# Peripherals.net
KiCad netlist of a schematic drawn in Altium Designer
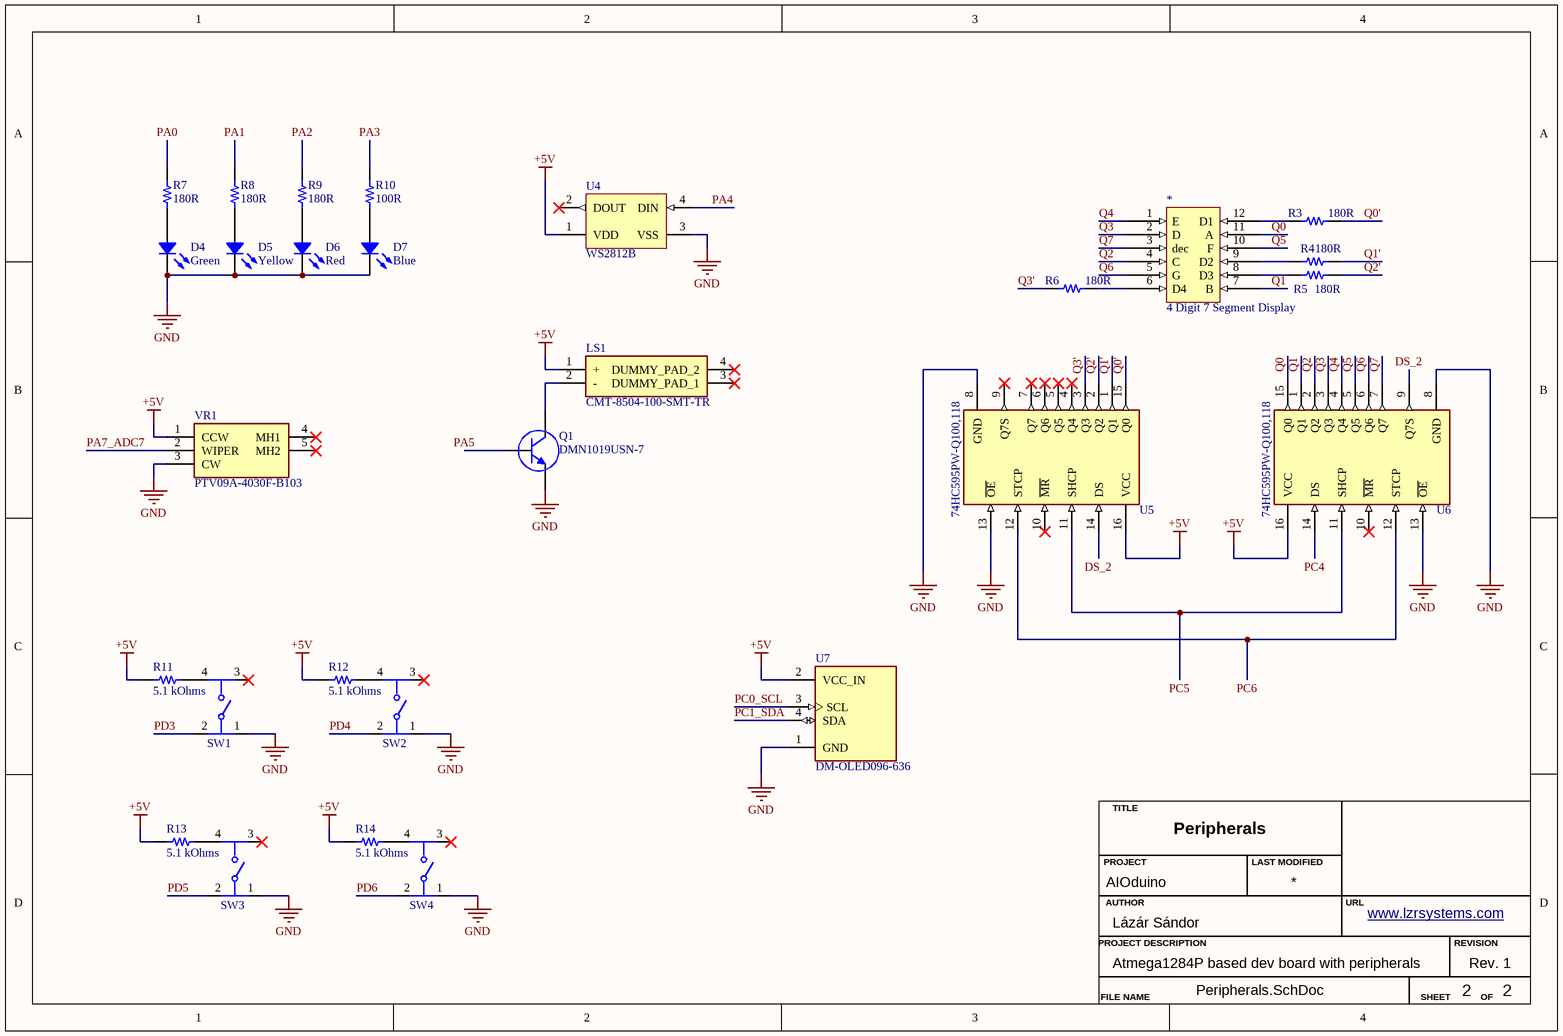
[diagram p0: Peripherals.SchDoc]

(export (version "E")
  (design (tool "Eeschema 10.0.6"))
  (components
    (comp (ref "*")
      (value "4 Digit 7 Segment Display")
      (footprint "4 Digit 7 Segment Display -Footprint-1")
      (description "3461AS 4 digit 7 segment display")
      (libsource (lib "Sandor Lazar") (part "4 Digit 7 Segment Display -Symbol-1"))
    )
    (comp (ref "D4")
      (value "Green")
      (footprint "LED 1206_3216 GREEN")
      (description "LED GREEN CLEAR 1206 SMD")
      (fields
        (field (name "PART NUMBER") "SML-LX1206SUGC-TR")
        (field (name "MANUFACTURER") "Lumex Opto/Components Inc.")
      )
      (libsource (lib "Celestial Altium Library - altium_library") (part "LED"))
    )
    (comp (ref "D5")
      (value "Yellow")
      (footprint "LED 1206_3216 YELLOW")
      (description "LED YELLOW CLEAR 1206 SMD")
      (fields (field (name "PART NUMBER") "SM1206NYC-IL") (field (name "MANUFACTURER") "Bivar Inc."))
      (libsource (lib "Celestial Altium Library - altium_library") (part "LED"))
    )
    (comp (ref "D6")
      (value "Red")
      (footprint "LED 1206_3216 RED")
      (description "LED RED CLEAR 1206 SMD")
      (fields
        (field (name "PART NUMBER") "BL-HUF33J-AV-TRB")
        (field (name "MANUFACTURER") "American Bright Optoelectronics Corporation")
      )
      (libsource (lib "Celestial Altium Library - altium_library") (part "LED"))
    )
    (comp (ref "D7")
      (value "Blue")
      (footprint "LED 1206_3216 BLUE")
      (description "LED BLUE CLEAR 1206 SMD")
      (fields
        (field (name "PART NUMBER") "SML-LX1206USBC-TR")
        (field (name "MANUFACTURER") "Lumex Opto/Components Inc.")
      )
      (libsource (lib "Celestial Altium Library - altium_library") (part "LED"))
    )
    (comp (ref "LS1")
      (value "CMT-8504-100-SMT-TR")
      (footprint "SamacSys:CMT8504100SMTTR")
      (description "Loudspeaker or Buzzer")
      (fields (field (name "MOUSER PART NUMBER") "490-CMT-8504100SMTTR"))
      (libsource (lib "*") (part "CMT-8504-100-SMT-TR"))
    )
    (comp (ref "Q1")
      (value "DMN1019USN-7")
      (footprint "FP-SC59-MFG")
      (libsource (lib "Sandor Lazar") (part "TRANS-NPN-3"))
    )
    (comp (ref "R3")
      (value "180R")
      (footprint "RES 0805_2012")
      (description "RES SMD 180 OHM 1% 1/2W 0805")
      (fields (field (name "PART NUMBER") "CRCW0805180RFKEAHP") (field (name "MANUFACTURER") "Vishay Dale"))
      (libsource (lib "Celestial Altium Library - altium_library") (part "Resistor"))
    )
    (comp (ref "R4")
      (value "180R")
      (footprint "RES 0805_2012")
      (description "RES SMD 180 OHM 1% 1/2W 0805")
      (fields (field (name "PART NUMBER") "CRCW0805180RFKEAHP") (field (name "MANUFACTURER") "Vishay Dale"))
      (libsource (lib "Celestial Altium Library - altium_library") (part "Resistor"))
    )
    (comp (ref "R5")
      (value "180R")
      (footprint "RES 0805_2012")
      (description "RES SMD 180 OHM 1% 1/2W 0805")
      (fields (field (name "PART NUMBER") "CRCW0805180RFKEAHP") (field (name "MANUFACTURER") "Vishay Dale"))
      (libsource (lib "Celestial Altium Library - altium_library") (part "Resistor"))
    )
    (comp (ref "R6")
      (value "180R")
      (footprint "RES 0805_2012")
      (description "RES SMD 180 OHM 1% 1/2W 0805")
      (fields (field (name "PART NUMBER") "CRCW0805180RFKEAHP") (field (name "MANUFACTURER") "Vishay Dale"))
      (libsource (lib "Celestial Altium Library - altium_library") (part "Resistor"))
    )
    (comp (ref "R7")
      (value "180R")
      (footprint "RES 0805_2012")
      (description "RES SMD 180 OHM 1% 1/2W 0805")
      (fields (field (name "PART NUMBER") "CRCW0805180RFKEAHP") (field (name "MANUFACTURER") "Vishay Dale"))
      (libsource (lib "Celestial Altium Library - altium_library") (part "Resistor"))
    )
    (comp (ref "R8")
      (value "180R")
      (footprint "RES 0805_2012")
      (description "RES SMD 180 OHM 1% 1/2W 0805")
      (fields (field (name "PART NUMBER") "CRCW0805180RFKEAHP") (field (name "MANUFACTURER") "Vishay Dale"))
      (libsource (lib "Celestial Altium Library - altium_library") (part "Resistor"))
    )
    (comp (ref "R9")
      (value "180R")
      (footprint "RES 0805_2012")
      (description "RES SMD 180 OHM 1% 1/2W 0805")
      (fields (field (name "PART NUMBER") "CRCW0805180RFKEAHP") (field (name "MANUFACTURER") "Vishay Dale"))
      (libsource (lib "Celestial Altium Library - altium_library") (part "Resistor"))
    )
    (comp (ref "R10")
      (value "100R")
      (footprint "RES 0805_2012")
      (description "RES SMD 100 OHM 1% 1/2W 0805")
      (fields (field (name "PART NUMBER") "RCS0805100RFKEA") (field (name "MANUFACTURER") "Vishay Dale"))
      (libsource (lib "Celestial Altium Library - altium_library") (part "Resistor"))
    )
    (comp (ref "R11")
      (value "5.1 kOhms")
      (footprint "RES 0805_2012")
      (description "RES 5.1K OHM 1% 1/8W 0805")
      (fields
        (field (name "PART NUMBER") "RMCF0805FT5K10")
        (field (name "MANUFACTURER") "Stackpole Electronics Inc")
      )
      (libsource (lib "Celestial Altium Library - altium_library") (part "Resistor"))
    )
    (comp (ref "R12")
      (value "5.1 kOhms")
      (footprint "RES 0805_2012")
      (description "RES 5.1K OHM 1% 1/8W 0805")
      (fields
        (field (name "PART NUMBER") "RMCF0805FT5K10")
        (field (name "MANUFACTURER") "Stackpole Electronics Inc")
      )
      (libsource (lib "Celestial Altium Library - altium_library") (part "Resistor"))
    )
    (comp (ref "R13")
      (value "5.1 kOhms")
      (footprint "RES 0805_2012")
      (description "RES 5.1K OHM 1% 1/8W 0805")
      (fields
        (field (name "PART NUMBER") "RMCF0805FT5K10")
        (field (name "MANUFACTURER") "Stackpole Electronics Inc")
      )
      (libsource (lib "Celestial Altium Library - altium_library") (part "Resistor"))
    )
    (comp (ref "R14")
      (value "5.1 kOhms")
      (footprint "RES 0805_2012")
      (description "RES 5.1K OHM 1% 1/8W 0805")
      (fields
        (field (name "PART NUMBER") "RMCF0805FT5K10")
        (field (name "MANUFACTURER") "Stackpole Electronics Inc")
      )
      (libsource (lib "Celestial Altium Library - altium_library") (part "Resistor"))
    )
    (comp (ref "SW1")
      (value "PTS526SK15SMTR2LFS")
      (footprint "FP-PTS526SK15SMTR2LFS-MFG")
      (description "Switch Tactile N.O. SPST Round Button Gull Wing 0.05A 12VDC 200000Cycles 2.45N SMD T/R")
      (libsource (lib "Sandor Lazar") (part "b8895f3f4cefb76e1819d2863dba89b"))
    )
    (comp (ref "SW2")
      (value "PTS526SK15SMTR2LFS")
      (footprint "FP-PTS526SK15SMTR2LFS-MFG")
      (description "Switch Tactile N.O. SPST Round Button Gull Wing 0.05A 12VDC 200000Cycles 2.45N SMD T/R")
      (libsource (lib "Sandor Lazar") (part "b8895f3f4cefb76e1819d2863dba89b"))
    )
    (comp (ref "SW3")
      (value "PTS526SK15SMTR2LFS")
      (footprint "FP-PTS526SK15SMTR2LFS-MFG")
      (description "Switch Tactile N.O. SPST Round Button Gull Wing 0.05A 12VDC 200000Cycles 2.45N SMD T/R")
      (libsource (lib "Sandor Lazar") (part "b8895f3f4cefb76e1819d2863dba89b"))
    )
    (comp (ref "SW4")
      (value "PTS526SK15SMTR2LFS")
      (footprint "FP-PTS526SK15SMTR2LFS-MFG")
      (description "Switch Tactile N.O. SPST Round Button Gull Wing 0.05A 12VDC 200000Cycles 2.45N SMD T/R")
      (libsource (lib "Sandor Lazar") (part "b8895f3f4cefb76e1819d2863dba89b"))
    )
    (comp (ref "U4")
      (value "WS2812B")
      (footprint "ADAI-WS2812B_V")
      (fields (field (name "MANUFACTURER") "Adafruit Industries"))
      (libsource (lib "Sandor Lazar") (part "ADAI-WS2812B-4"))
    )
    (comp (ref "U5")
      (value "74HC595PW-Q100,118")
      (footprint "FP-SOT403-1-IPC_A")
      (description "Serial In Parallel Out, HC/UH Series, 8-Bit, Right Direction, True Output, CMOS, PDSO16")
      (libsource (lib "") (part "35014dcb5ee7218ec7bb80311b7c79e_1"))
    )
    (comp (ref "U6")
      (value "74HC595PW-Q100,118")
      (footprint "FP-SOT403-1-IPC_A")
      (description "Serial In Parallel Out, HC/UH Series, 8-Bit, Right Direction, True Output, CMOS, PDSO16")
      (libsource (lib "Sandor Lazar") (part "35014dcb5ee7218ec7bb80311b7c79e"))
    )
    (comp (ref "U7")
      (value "DM-OLED096-636")
      (footprint "MODULE_DM-OLED096-636")
      (description "0.96â€ 128 X 64 MONOCHROME GRAPHIC OLED DISPLAY MODULE - I2C")
      (fields (field (name "MF") "Display Module"))
      (libsource (lib "Sandor Lazar") (part "DM-OLED096-636"))
    )
    (comp (ref "VR1")
      (value "PTV09A-4030F-B103")
      (footprint "SamacSys:PTV09A4030FB103")
      (description "Variable Resistor")
      (fields (field (name "MOUSER PART NUMBER") "652-PTV09A4030FB103"))
      (libsource (lib "*") (part "PTV09A-4030F-B103"))
    )
  )
  (nets
    (net (code "1") (name "+5V") (class "Default")
      (node (ref "LS1") (pin "1") (pinfunction "+_1") (pintype "passive"))
      (node (ref "R11") (pin "2") (pinfunction "2_2") (pintype "passive"))
      (node (ref "R12") (pin "2") (pinfunction "2_2") (pintype "passive"))
      (node (ref "R13") (pin "2") (pinfunction "2_2") (pintype "passive"))
      (node (ref "R14") (pin "2") (pinfunction "2_2") (pintype "passive"))
      (node (ref "U4") (pin "1") (pinfunction "VDD_1") (pintype "passive"))
      (node (ref "U5") (pin "16") (pinfunction "VCC_16") (pintype "passive"))
      (node (ref "U6") (pin "16") (pinfunction "VCC_16") (pintype "passive"))
      (node (ref "U7") (pin "2") (pinfunction "VCC_IN_2") (pintype "power_in"))
      (node (ref "VR1") (pin "1") (pinfunction "CCW_1") (pintype "passive"))
    )
    (net (code "2") (name "/DS_2") (class "Default")
      (node (ref "U5") (pin "14") (pinfunction "DS_14") (pintype "input"))
      (node (ref "U6") (pin "9") (pinfunction "Q7S_9") (pintype "output"))
    )
    (net (code "3") (name "/PA0") (class "Default")
      (node (ref "R7") (pin "2") (pinfunction "2_2") (pintype "passive"))
    )
    (net (code "4") (name "/PA1") (class "Default")
      (node (ref "R8") (pin "2") (pinfunction "2_2") (pintype "passive"))
    )
    (net (code "5") (name "/PA2") (class "Default")
      (node (ref "R9") (pin "2") (pinfunction "2_2") (pintype "passive"))
    )
    (net (code "6") (name "/PA3") (class "Default")
      (node (ref "R10") (pin "2") (pinfunction "2_2") (pintype "passive"))
    )
    (net (code "7") (name "/PA4") (class "Default")
      (node (ref "U4") (pin "4") (pinfunction "DIN_4") (pintype "input"))
    )
    (net (code "8") (name "/PA5") (class "Default")
      (node (ref "Q1") (pin "2") (pinfunction "B_2") (pintype "passive"))
    )
    (net (code "9") (name "/PA7_ADC7") (class "Default")
      (node (ref "VR1") (pin "2") (pinfunction "WIPER_2") (pintype "passive"))
    )
    (net (code "10") (name "/PC0_SCL") (class "Default")
      (node (ref "U7") (pin "3") (pinfunction "SCL_3") (pintype "input"))
    )
    (net (code "11") (name "/PC1_SDA") (class "Default")
      (node (ref "U7") (pin "4") (pinfunction "SDA_4") (pintype "bidirectional"))
    )
    (net (code "12") (name "/PC4") (class "Default")
      (node (ref "U6") (pin "14") (pinfunction "DS_14") (pintype "input"))
    )
    (net (code "13") (name "/PC5") (class "Default")
      (node (ref "U5") (pin "11") (pinfunction "SHCP_11") (pintype "input"))
      (node (ref "U6") (pin "11") (pinfunction "SHCP_11") (pintype "input"))
    )
    (net (code "14") (name "/PC6") (class "Default")
      (node (ref "U5") (pin "12") (pinfunction "STCP_12") (pintype "input"))
      (node (ref "U6") (pin "12") (pinfunction "STCP_12") (pintype "input"))
    )
    (net (code "15") (name "/PD3") (class "Default")
      (node (ref "SW1") (pin "2") (pinfunction "2_2") (pintype "passive"))
    )
    (net (code "16") (name "/PD4") (class "Default")
      (node (ref "SW2") (pin "2") (pinfunction "2_2") (pintype "passive"))
    )
    (net (code "17") (name "/PD5") (class "Default")
      (node (ref "SW3") (pin "2") (pinfunction "2_2") (pintype "passive"))
    )
    (net (code "18") (name "/PD6") (class "Default")
      (node (ref "SW4") (pin "2") (pinfunction "2_2") (pintype "passive"))
    )
    (net (code "19") (name "/Q0") (class "Default")
      (node (ref "*") (pin "11") (pinfunction "A_11") (pintype "input"))
      (node (ref "U6") (pin "15") (pinfunction "Q0_15") (pintype "output"))
    )
    (net (code "20") (name "/Q0'") (class "Default")
      (node (ref "R3") (pin "1") (pinfunction "1_1") (pintype "passive"))
      (node (ref "U5") (pin "15") (pinfunction "Q0_15") (pintype "output"))
    )
    (net (code "21") (name "/Q1") (class "Default")
      (node (ref "*") (pin "7") (pinfunction "B_7") (pintype "input"))
      (node (ref "U6") (pin "1") (pinfunction "Q1_1") (pintype "output"))
    )
    (net (code "22") (name "/Q1'") (class "Default")
      (node (ref "R4") (pin "2") (pinfunction "2_2") (pintype "passive"))
      (node (ref "U5") (pin "1") (pinfunction "Q1_1") (pintype "output"))
    )
    (net (code "23") (name "/Q2") (class "Default")
      (node (ref "*") (pin "4") (pinfunction "C_4") (pintype "input"))
      (node (ref "U6") (pin "2") (pinfunction "Q2_2") (pintype "output"))
    )
    (net (code "24") (name "/Q2'") (class "Default")
      (node (ref "R5") (pin "2") (pinfunction "2_2") (pintype "passive"))
      (node (ref "U5") (pin "2") (pinfunction "Q2_2") (pintype "output"))
    )
    (net (code "25") (name "/Q3") (class "Default")
      (node (ref "*") (pin "2") (pinfunction "D_2") (pintype "input"))
      (node (ref "U6") (pin "3") (pinfunction "Q3_3") (pintype "output"))
    )
    (net (code "26") (name "/Q3'") (class "Default")
      (node (ref "R6") (pin "2") (pinfunction "2_2") (pintype "passive"))
      (node (ref "U5") (pin "3") (pinfunction "Q3_3") (pintype "output"))
    )
    (net (code "27") (name "/Q4") (class "Default")
      (node (ref "*") (pin "1") (pinfunction "E_1") (pintype "input"))
      (node (ref "U6") (pin "4") (pinfunction "Q4_4") (pintype "output"))
    )
    (net (code "28") (name "/Q5") (class "Default")
      (node (ref "*") (pin "10") (pinfunction "F_10") (pintype "input"))
      (node (ref "U6") (pin "5") (pinfunction "Q5_5") (pintype "output"))
    )
    (net (code "29") (name "/Q6") (class "Default")
      (node (ref "*") (pin "5") (pinfunction "G_5") (pintype "input"))
      (node (ref "U6") (pin "6") (pinfunction "Q6_6") (pintype "output"))
    )
    (net (code "30") (name "/Q7") (class "Default")
      (node (ref "*") (pin "3") (pinfunction "dec_3") (pintype "input"))
      (node (ref "U6") (pin "7") (pinfunction "Q7_7") (pintype "output"))
    )
    (net (code "31") (name "GND") (class "Default")
      (node (ref "D4") (pin "2") (pinfunction "2_2") (pintype "passive"))
      (node (ref "D5") (pin "2") (pinfunction "2_2") (pintype "passive"))
      (node (ref "D6") (pin "2") (pinfunction "2_2") (pintype "passive"))
      (node (ref "D7") (pin "2") (pinfunction "2_2") (pintype "passive"))
      (node (ref "Q1") (pin "1") (pinfunction "E_1") (pintype "passive"))
      (node (ref "SW1") (pin "1") (pinfunction "1_1") (pintype "passive"))
      (node (ref "SW2") (pin "1") (pinfunction "1_1") (pintype "passive"))
      (node (ref "SW3") (pin "1") (pinfunction "1_1") (pintype "passive"))
      (node (ref "SW4") (pin "1") (pinfunction "1_1") (pintype "passive"))
      (node (ref "U4") (pin "3") (pinfunction "VSS_3") (pintype "passive"))
      (node (ref "U5") (pin "13") (pinfunction "~{OE}_13") (pintype "input"))
      (node (ref "U5") (pin "8") (pinfunction "GND_8") (pintype "passive"))
      (node (ref "U6") (pin "13") (pinfunction "~{OE}_13") (pintype "input"))
      (node (ref "U6") (pin "8") (pinfunction "GND_8") (pintype "passive"))
      (node (ref "U7") (pin "1") (pinfunction "GND_1") (pintype "power_in"))
      (node (ref "VR1") (pin "3") (pinfunction "CW_3") (pintype "passive"))
    )
    (net (code "32") (name "Net-(*-D1)") (class "Default")
      (node (ref "*") (pin "12") (pinfunction "D1_12") (pintype "input"))
      (node (ref "R3") (pin "2") (pinfunction "2_2") (pintype "passive"))
    )
    (net (code "33") (name "Net-(*-D2)") (class "Default")
      (node (ref "*") (pin "9") (pinfunction "D2_9") (pintype "input"))
      (node (ref "R4") (pin "1") (pinfunction "1_1") (pintype "passive"))
    )
    (net (code "34") (name "Net-(*-D3)") (class "Default")
      (node (ref "*") (pin "8") (pinfunction "D3_8") (pintype "input"))
      (node (ref "R5") (pin "1") (pinfunction "1_1") (pintype "passive"))
    )
    (net (code "35") (name "Net-(*-D4)") (class "Default")
      (node (ref "*") (pin "6") (pinfunction "D4_6") (pintype "input"))
      (node (ref "R6") (pin "1") (pinfunction "1_1") (pintype "passive"))
    )
    (net (code "36") (name "Net-(D4-Pad1)") (class "Default")
      (node (ref "D4") (pin "1") (pinfunction "1_1") (pintype "passive"))
      (node (ref "R7") (pin "1") (pinfunction "1_1") (pintype "passive"))
    )
    (net (code "37") (name "Net-(D5-Pad1)") (class "Default")
      (node (ref "D5") (pin "1") (pinfunction "1_1") (pintype "passive"))
      (node (ref "R8") (pin "1") (pinfunction "1_1") (pintype "passive"))
    )
    (net (code "38") (name "Net-(D6-Pad1)") (class "Default")
      (node (ref "D6") (pin "1") (pinfunction "1_1") (pintype "passive"))
      (node (ref "R9") (pin "1") (pinfunction "1_1") (pintype "passive"))
    )
    (net (code "39") (name "Net-(D7-Pad1)") (class "Default")
      (node (ref "D7") (pin "1") (pinfunction "1_1") (pintype "passive"))
      (node (ref "R10") (pin "1") (pinfunction "1_1") (pintype "passive"))
    )
    (net (code "40") (name "Net-(LS1--)") (class "Default")
      (node (ref "LS1") (pin "2") (pinfunction "-_2") (pintype "passive"))
      (node (ref "Q1") (pin "3") (pinfunction "C_3") (pintype "passive"))
    )
    (net (code "41") (name "Net-(R11-Pad1)") (class "Default")
      (node (ref "R11") (pin "1") (pinfunction "1_1") (pintype "passive"))
      (node (ref "SW1") (pin "4") (pinfunction "4_4") (pintype "passive"))
    )
    (net (code "42") (name "Net-(R12-Pad1)") (class "Default")
      (node (ref "R12") (pin "1") (pinfunction "1_1") (pintype "passive"))
      (node (ref "SW2") (pin "4") (pinfunction "4_4") (pintype "passive"))
    )
    (net (code "43") (name "Net-(R13-Pad1)") (class "Default")
      (node (ref "R13") (pin "1") (pinfunction "1_1") (pintype "passive"))
      (node (ref "SW3") (pin "4") (pinfunction "4_4") (pintype "passive"))
    )
    (net (code "44") (name "Net-(R14-Pad1)") (class "Default")
      (node (ref "R14") (pin "1") (pinfunction "1_1") (pintype "passive"))
      (node (ref "SW4") (pin "4") (pinfunction "4_4") (pintype "passive"))
    )
    (net (code "45") (name "unconnected-(LS1-DUMMY_PAD_1-Pad3)") (class "Default")
      (node (ref "LS1") (pin "3") (pinfunction "DUMMY_PAD_1_3") (pintype "passive+no_connect"))
    )
    (net (code "46") (name "unconnected-(LS1-DUMMY_PAD_2-Pad4)") (class "Default")
      (node (ref "LS1") (pin "4") (pinfunction "DUMMY_PAD_2_4") (pintype "passive+no_connect"))
    )
    (net (code "47") (name "unconnected-(SW1-Pad3)") (class "Default")
      (node (ref "SW1") (pin "3") (pinfunction "3_3") (pintype "passive+no_connect"))
    )
    (net (code "48") (name "unconnected-(SW2-Pad3)") (class "Default")
      (node (ref "SW2") (pin "3") (pinfunction "3_3") (pintype "passive+no_connect"))
    )
    (net (code "49") (name "unconnected-(SW3-Pad3)") (class "Default")
      (node (ref "SW3") (pin "3") (pinfunction "3_3") (pintype "passive+no_connect"))
    )
    (net (code "50") (name "unconnected-(SW4-Pad3)") (class "Default")
      (node (ref "SW4") (pin "3") (pinfunction "3_3") (pintype "passive+no_connect"))
    )
    (net (code "51") (name "unconnected-(U4-DOUT-Pad2)") (class "Default")
      (node (ref "U4") (pin "2") (pinfunction "DOUT_2") (pintype "output+no_connect"))
    )
    (net (code "52") (name "unconnected-(U5-Q4-Pad4)") (class "Default")
      (node (ref "U5") (pin "4") (pinfunction "Q4_4") (pintype "output+no_connect"))
    )
    (net (code "53") (name "unconnected-(U5-Q5-Pad5)") (class "Default")
      (node (ref "U5") (pin "5") (pinfunction "Q5_5") (pintype "output+no_connect"))
    )
    (net (code "54") (name "unconnected-(U5-Q6-Pad6)") (class "Default")
      (node (ref "U5") (pin "6") (pinfunction "Q6_6") (pintype "output+no_connect"))
    )
    (net (code "55") (name "unconnected-(U5-Q7-Pad7)") (class "Default")
      (node (ref "U5") (pin "7") (pinfunction "Q7_7") (pintype "output+no_connect"))
    )
    (net (code "56") (name "unconnected-(U5-Q7S-Pad9)") (class "Default")
      (node (ref "U5") (pin "9") (pinfunction "Q7S_9") (pintype "output+no_connect"))
    )
    (net (code "57") (name "unconnected-(U5-~{MR}-Pad10)") (class "Default")
      (node (ref "U5") (pin "10") (pinfunction "~{MR}_10") (pintype "input+no_connect"))
    )
    (net (code "58") (name "unconnected-(U6-~{MR}-Pad10)") (class "Default")
      (node (ref "U6") (pin "10") (pinfunction "~{MR}_10") (pintype "input+no_connect"))
    )
    (net (code "59") (name "unconnected-(VR1-MH1-Pad4)") (class "Default")
      (node (ref "VR1") (pin "4") (pinfunction "MH1_4") (pintype "passive+no_connect"))
    )
    (net (code "60") (name "unconnected-(VR1-MH2-Pad5)") (class "Default")
      (node (ref "VR1") (pin "5") (pinfunction "MH2_5") (pintype "passive+no_connect"))
    )
  )
)
